# SCH_chassis-555_2025-10-31.net
KiCad netlist of a schematic drawn in EasyEDA
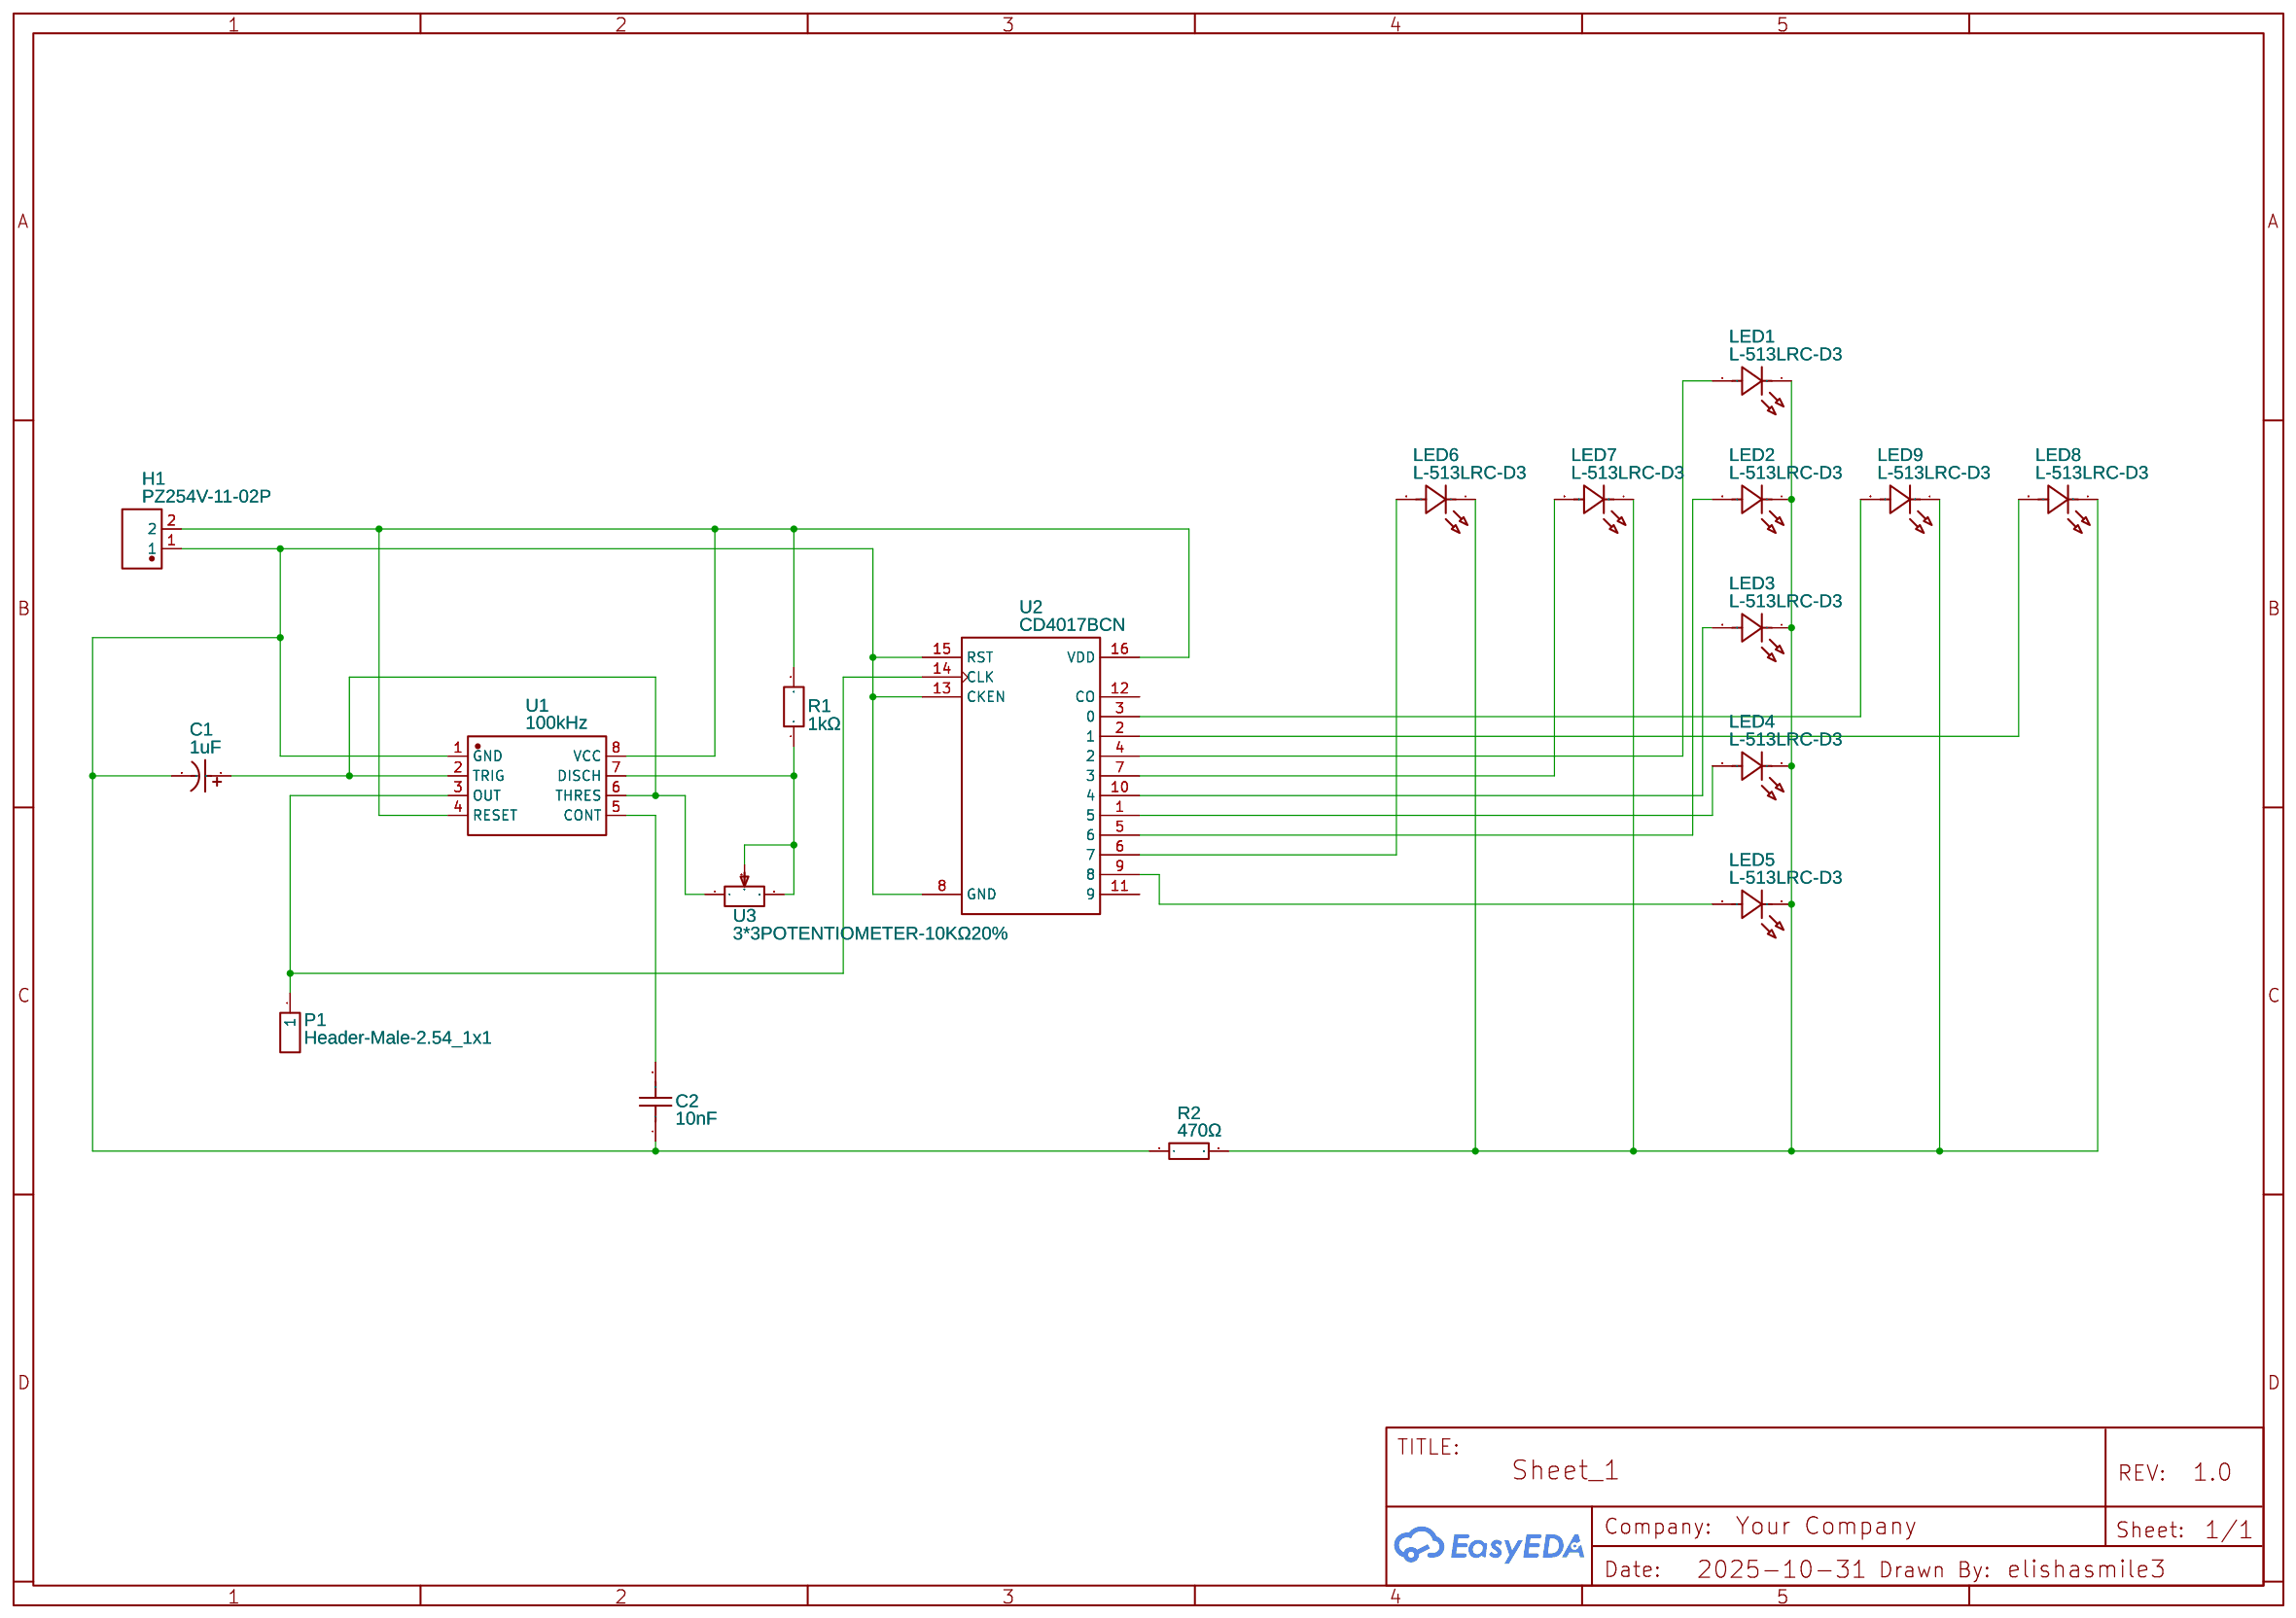
[diagram p0: schematic sheet]

(export (version "E")
  (design (tool "Eeschema 10.0.6"))
  (components
    (comp (ref "C1")
      (value "1uF")
      (fields (field (name "Manufacturer Part") "KF010M050C110A") (field (name "Manufacturer") "CapXon(丰宾)"))
      (libsource (lib "") (part "KF010M050C110A"))
    )
    (comp (ref "C2")
      (value "10nF")
      (fields (field (name "Manufacturer Part") "N09F1B103MN0B0S0N0") (field (name "Manufacturer") "STE(松田)"))
      (libsource (lib "") (part "N09F1B103MN0B0S0N0"))
    )
    (comp (ref "H1")
      (value "PZ254V-11-02P")
      (fields (field (name "Manufacturer") "XFCN(兴飞)"))
      (libsource (lib "") (part "PZ254V-11-02P"))
    )
    (comp (ref "LED1")
      (value "L-513LRC-D3")
      (fields (field (name "Manufacturer") "PARALIGHT(光鼎)"))
      (libsource (lib "") (part "L-513LRC-D3"))
    )
    (comp (ref "LED2")
      (value "L-513LRC-D3")
      (fields (field (name "Manufacturer") "PARALIGHT(光鼎)"))
      (libsource (lib "") (part "L-513LRC-D3"))
    )
    (comp (ref "LED3")
      (value "L-513LRC-D3")
      (fields (field (name "Manufacturer") "PARALIGHT(光鼎)"))
      (libsource (lib "") (part "L-513LRC-D3"))
    )
    (comp (ref "LED4")
      (value "L-513LRC-D3")
      (fields (field (name "Manufacturer") "PARALIGHT(光鼎)"))
      (libsource (lib "") (part "L-513LRC-D3"))
    )
    (comp (ref "LED5")
      (value "L-513LRC-D3")
      (fields (field (name "Manufacturer") "PARALIGHT(光鼎)"))
      (libsource (lib "") (part "L-513LRC-D3"))
    )
    (comp (ref "LED6")
      (value "L-513LRC-D3")
      (fields (field (name "Manufacturer") "PARALIGHT(光鼎)"))
      (libsource (lib "") (part "L-513LRC-D3"))
    )
    (comp (ref "LED7")
      (value "L-513LRC-D3")
      (fields (field (name "Manufacturer") "PARALIGHT(光鼎)"))
      (libsource (lib "") (part "L-513LRC-D3"))
    )
    (comp (ref "LED8")
      (value "L-513LRC-D3")
      (fields (field (name "Manufacturer") "PARALIGHT(光鼎)"))
      (libsource (lib "") (part "L-513LRC-D3"))
    )
    (comp (ref "LED9")
      (value "L-513LRC-D3")
      (fields (field (name "Manufacturer") "PARALIGHT(光鼎)"))
      (libsource (lib "") (part "L-513LRC-D3"))
    )
    (comp (ref "P1")
      (value "Header-Male-2.54_1x1")
      (fields (field (name "Manufacturer Part") "2.54-1*1P针") (field (name "Manufacturer") "BOOMELE(博穆精密)"))
      (libsource (lib "") (part "Header-Male-2.54_1x1"))
    )
    (comp (ref "R1")
      (value "1kΩ")
      (fields (field (name "Manufacturer Part") "MF1/4W-1KΩ±1%T52") (field (name "Manufacturer") "华星机电"))
      (libsource (lib "") (part "MF1/4W-1KΩ±1%T52"))
    )
    (comp (ref "R2")
      (value "470Ω")
      (fields
        (field (name "Manufacturer Part") "MFR0W4F4700A50")
        (field (name "Manufacturer") "UNI-ROYAL(厚声)")
      )
      (libsource (lib "") (part "MFR0W4F4700A50"))
    )
    (comp (ref "U1")
      (value "100kHz")
      (fields (field (name "Manufacturer Part") "NE555P") (field (name "Manufacturer") "TI(德州仪器)"))
      (libsource (lib "") (part "NE555P"))
    )
    (comp (ref "U2") (value "CD4017BCN") (libsource (lib "") (part "CD4017BCN")))
    (comp (ref "U3")
      (value "3*3POTENTIOMETER-10KΩ20%")
      (fields (field (name "Manufacturer Part") "3*3Potentiometer-10kΩ20%"))
      (libsource (lib "") (part "3*3POTENTIOMETER-10KΩ20%"))
    )
  )
  (nets
    (net (code "1") (name "Net-(LED1-A)") (class "Default")
      (node (ref "LED1") (pin "2") (pinfunction "A_2") (pintype "unspecified"))
      (node (ref "U2") (pin "4") (pinfunction "2_4") (pintype "output"))
    )
    (net (code "2") (name "Net-(LED1-K)") (class "Default")
      (node (ref "LED1") (pin "1") (pinfunction "K_1") (pintype "unspecified"))
      (node (ref "LED2") (pin "1") (pinfunction "K_1") (pintype "unspecified"))
      (node (ref "LED3") (pin "1") (pinfunction "K_1") (pintype "unspecified"))
      (node (ref "LED4") (pin "1") (pinfunction "K_1") (pintype "unspecified"))
      (node (ref "LED5") (pin "1") (pinfunction "K_1") (pintype "unspecified"))
      (node (ref "LED6") (pin "1") (pinfunction "K_1") (pintype "unspecified"))
      (node (ref "LED7") (pin "1") (pinfunction "K_1") (pintype "unspecified"))
      (node (ref "LED8") (pin "1") (pinfunction "K_1") (pintype "unspecified"))
      (node (ref "LED9") (pin "1") (pinfunction "K_1") (pintype "unspecified"))
      (node (ref "R2") (pin "2") (pinfunction "2_2") (pintype "input"))
    )
    (net (code "3") (name "Net-(LED2-A)") (class "Default")
      (node (ref "LED2") (pin "2") (pinfunction "A_2") (pintype "unspecified"))
      (node (ref "U2") (pin "5") (pinfunction "6_5") (pintype "output"))
    )
    (net (code "4") (name "Net-(LED3-A)") (class "Default")
      (node (ref "LED3") (pin "2") (pinfunction "A_2") (pintype "unspecified"))
      (node (ref "U2") (pin "10") (pinfunction "4_10") (pintype "output"))
    )
    (net (code "5") (name "Net-(LED4-A)") (class "Default")
      (node (ref "LED4") (pin "2") (pinfunction "A_2") (pintype "unspecified"))
      (node (ref "U2") (pin "1") (pinfunction "5_1") (pintype "output"))
    )
    (net (code "6") (name "Net-(LED5-A)") (class "Default")
      (node (ref "LED5") (pin "2") (pinfunction "A_2") (pintype "unspecified"))
      (node (ref "U2") (pin "9") (pinfunction "8_9") (pintype "output"))
    )
    (net (code "7") (name "Net-(LED6-A)") (class "Default")
      (node (ref "LED6") (pin "2") (pinfunction "A_2") (pintype "unspecified"))
      (node (ref "U2") (pin "6") (pinfunction "7_6") (pintype "output"))
    )
    (net (code "8") (name "Net-(LED7-A)") (class "Default")
      (node (ref "LED7") (pin "2") (pinfunction "A_2") (pintype "unspecified"))
      (node (ref "U2") (pin "7") (pinfunction "3_7") (pintype "output"))
    )
    (net (code "9") (name "Net-(LED8-A)") (class "Default")
      (node (ref "LED8") (pin "2") (pinfunction "A_2") (pintype "unspecified"))
      (node (ref "U2") (pin "2") (pinfunction "1_2") (pintype "output"))
    )
    (net (code "10") (name "Net-(LED9-A)") (class "Default")
      (node (ref "LED9") (pin "2") (pinfunction "A_2") (pintype "unspecified"))
      (node (ref "U2") (pin "3") (pinfunction "0_3") (pintype "output"))
    )
    (net (code "11") (name "Net-(U1-CONT)") (class "Default")
      (node (ref "C2") (pin "2") (pinfunction "2_2") (pintype "unspecified"))
      (node (ref "U1") (pin "5") (pinfunction "CONT_5") (pintype "unspecified"))
    )
    (net (code "12") (name "Net-(U1-DISCH)") (class "Default")
      (node (ref "R1") (pin "1") (pinfunction "1_1") (pintype "unspecified"))
      (node (ref "U1") (pin "7") (pinfunction "DISCH_7") (pintype "unspecified"))
      (node (ref "U3") (pin "2") (pinfunction "2_2") (pintype "input"))
      (node (ref "U3") (pin "3") (pinfunction "3_3") (pintype "input"))
    )
    (net (code "13") (name "Net-(U1-GND)") (class "Default")
      (node (ref "C1") (pin "2") (pinfunction "2_2") (pintype "input"))
      (node (ref "C2") (pin "1") (pinfunction "1_1") (pintype "unspecified"))
      (node (ref "H1") (pin "1") (pinfunction "1_1") (pintype "unspecified"))
      (node (ref "R2") (pin "1") (pinfunction "1_1") (pintype "input"))
      (node (ref "U1") (pin "1") (pinfunction "GND_1") (pintype "unspecified"))
      (node (ref "U2") (pin "13") (pinfunction "CKEN_13") (pintype "unspecified"))
      (node (ref "U2") (pin "15") (pinfunction "RST_15") (pintype "unspecified"))
      (node (ref "U2") (pin "8") (pinfunction "GND_8") (pintype "passive"))
    )
    (net (code "14") (name "Net-(U1-OUT)") (class "Default")
      (node (ref "P1") (pin "1") (pinfunction "1_1") (pintype "input"))
      (node (ref "U1") (pin "3") (pinfunction "OUT_3") (pintype "unspecified"))
      (node (ref "U2") (pin "14") (pinfunction "CLK_14") (pintype "unspecified"))
    )
    (net (code "15") (name "Net-(U1-RESET)") (class "Default")
      (node (ref "H1") (pin "2") (pinfunction "2_2") (pintype "unspecified"))
      (node (ref "R1") (pin "2") (pinfunction "2_2") (pintype "unspecified"))
      (node (ref "U1") (pin "4") (pinfunction "RESET_4") (pintype "unspecified"))
      (node (ref "U1") (pin "8") (pinfunction "VCC_8") (pintype "unspecified"))
      (node (ref "U2") (pin "16") (pinfunction "VDD_16") (pintype "passive"))
    )
    (net (code "16") (name "Net-(U1-THRES)") (class "Default")
      (node (ref "C1") (pin "1") (pinfunction "1_1") (pintype "input"))
      (node (ref "U1") (pin "2") (pinfunction "TRIG_2") (pintype "unspecified"))
      (node (ref "U1") (pin "6") (pinfunction "THRES_6") (pintype "unspecified"))
      (node (ref "U3") (pin "1") (pinfunction "1_1") (pintype "input"))
    )
    (net (code "17") (name "unconnected-(U2-9-Pad11)") (class "Default")
      (node (ref "U2") (pin "11") (pinfunction "9_11") (pintype "output"))
    )
    (net (code "18") (name "unconnected-(U2-CO-Pad12)") (class "Default")
      (node (ref "U2") (pin "12") (pinfunction "CO_12") (pintype "output"))
    )
  )
)
